# rs485.net
KiCad netlist of a schematic drawn in Altium Designer
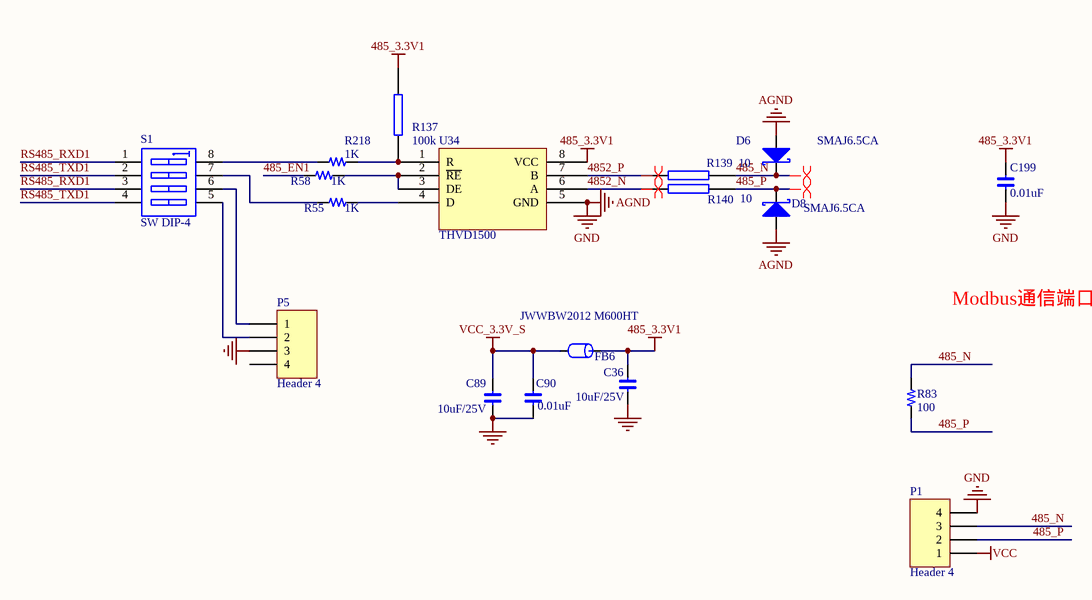
[diagram p0: rs485.SchDoc]

(export (version "E")
  (design (tool "Eeschema 10.0.6"))
  (components
    (comp (ref "C36")
      (value "10uF/25V")
      (footprint "0603C")
      (description "C")
      (libsource (lib "Schlib_20110825") (part "C"))
    )
    (comp (ref "C89")
      (value "10uF/25V")
      (footprint "0603C")
      (description "C")
      (libsource (lib "Schlib_20110825") (part "C"))
    )
    (comp (ref "C90")
      (value "0.01uF")
      (footprint "0603C")
      (description "C")
      (libsource (lib "Schlib_20110825") (part "C"))
    )
    (comp (ref "C199")
      (value "0.01uF")
      (footprint "0603C")
      (description "C")
      (libsource (lib "Schlib_20110825") (part "C"))
    )
    (comp (ref "D6")
      (value "SMAJ6.5CA")
      (footprint "SMA")
      (description "Schottky Diode")
      (libsource (lib "*") (part "DIODE S"))
    )
    (comp (ref "D8")
      (value "SMAJ6.5CA")
      (footprint "SMA")
      (description "Schottky Diode")
      (libsource (lib "*") (part "DIODE S"))
    )
    (comp (ref "FB6")
      (value "JWWBW2012 M600HT")
      (footprint "0805CZ")
      (libsource (lib "Schlib_20110825") (part "FB"))
    )
    (comp (ref "P1")
      (value "Header 4")
      (footprint "4X2.54MMZ")
      (description "Header, 4-Pin")
      (fields (field (name "PUBLISHER") "Altium Limited"))
      (libsource (lib "Miscellaneous Connectors") (part "Header 4"))
    )
    (comp (ref "P5")
      (value "Header 4")
      (footprint "4X2.54MMZ")
      (description "Header, 4-Pin")
      (fields (field (name "PUBLISHER") "Altium Limited"))
      (libsource (lib "") (part "Header 4_1"))
    )
    (comp (ref "R55") (value "1K") (footprint "0603R") (description "R") (libsource (lib "JRJ_1") (part "R")))
    (comp (ref "R58") (value "1K") (footprint "0603R") (description "R") (libsource (lib "JRJ_1") (part "R")))
    (comp (ref "R83")
      (value "100")
      (footprint "0603R")
      (description "R")
      (libsource (lib "JRJ_1") (part "R"))
    )
    (comp (ref "R137") (value "100k") (footprint "0603R") (libsource (lib "*") (part "RES2")))
    (comp (ref "R139") (value "10") (footprint "1206R") (libsource (lib "*") (part "RES2")))
    (comp (ref "R140") (value "10") (footprint "1206R") (libsource (lib "*") (part "RES2")))
    (comp (ref "R218")
      (value "1K")
      (footprint "0603R")
      (description "R")
      (libsource (lib "JRJ_1") (part "R"))
    )
    (comp (ref "S1")
      (value "SW DIP-4")
      (footprint "SW_SMT_8")
      (description "DIP Switch, 4 Position, SPST")
      (fields (field (name "PUBLISHER") "Altium Limited"))
      (libsource (lib "Miscellaneous Devices") (part "SW DIP-4"))
    )
    (comp (ref "U34") (value "THVD1500") (footprint "so-8") (libsource (lib "Schlib1") (part "SN65HVD06D")))
  )
  (nets
    (net (code "1") (name "/485_EN1") (class "Default") (node (ref "R58") (pin "2") (pintype "passive")))
    (net (code "2") (name "/485_N") (class "Default")
      (node (ref "D6") (pin "2") (pinfunction "K_2") (pintype "passive"))
      (node (ref "P1") (pin "3") (pinfunction "3_3") (pintype "passive"))
      (node (ref "R139") (pin "1") (pinfunction "1_1") (pintype "passive"))
      (node (ref "R83") (pin "2") (pintype "passive"))
    )
    (net (code "3") (name "/485_P") (class "Default")
      (node (ref "D8") (pin "2") (pinfunction "K_2") (pintype "passive"))
      (node (ref "P1") (pin "2") (pinfunction "2_2") (pintype "passive"))
      (node (ref "R140") (pin "1") (pinfunction "1_1") (pintype "passive"))
      (node (ref "R83") (pin "1") (pintype "passive"))
    )
    (net (code "4") (name "/4852_N") (class "Default")
      (node (ref "R140") (pin "2") (pinfunction "2_2") (pintype "passive"))
      (node (ref "U34") (pin "6") (pinfunction "A_6") (pintype "passive"))
    )
    (net (code "5") (name "/4852_P") (class "Default")
      (node (ref "R139") (pin "2") (pinfunction "2_2") (pintype "passive"))
      (node (ref "U34") (pin "7") (pinfunction "B_7") (pintype "passive"))
    )
    (net (code "6") (name "/RS485_RXD1") (class "Default")
      (node (ref "S1") (pin "1") (pinfunction "A1_1") (pintype "passive"))
      (node (ref "S1") (pin "3") (pinfunction "A3_3") (pintype "passive"))
    )
    (net (code "7") (name "/RS485_TXD1") (class "Default")
      (node (ref "S1") (pin "2") (pinfunction "A2_2") (pintype "passive"))
      (node (ref "S1") (pin "4") (pinfunction "A4_4") (pintype "passive"))
    )
    (net (code "8") (name "485_3.3V1") (class "Default")
      (node (ref "C199") (pin "2") (pintype "passive"))
      (node (ref "C36") (pin "2") (pintype "passive"))
      (node (ref "FB6") (pin "1") (pintype "passive"))
      (node (ref "R137") (pin "2") (pinfunction "2_2") (pintype "passive"))
      (node (ref "U34") (pin "8") (pinfunction "VCC_8") (pintype "passive"))
    )
    (net (code "9") (name "AGND") (class "Default")
      (node (ref "C199") (pin "1") (pintype "passive"))
      (node (ref "C36") (pin "1") (pintype "passive"))
      (node (ref "C89") (pin "1") (pintype "passive"))
      (node (ref "C90") (pin "1") (pintype "passive"))
      (node (ref "D6") (pin "1") (pinfunction "A_1") (pintype "passive"))
      (node (ref "D8") (pin "1") (pinfunction "A_1") (pintype "passive"))
      (node (ref "P1") (pin "4") (pinfunction "4_4") (pintype "passive"))
      (node (ref "P5") (pin "3") (pinfunction "3_3") (pintype "passive"))
      (node (ref "U34") (pin "5") (pinfunction "GND_5") (pintype "passive"))
    )
    (net (code "10") (name "Net-(S1-B1)") (class "Default")
      (node (ref "R218") (pin "2") (pintype "passive"))
      (node (ref "S1") (pin "8") (pinfunction "B1_8") (pintype "passive"))
    )
    (net (code "11") (name "Net-(S1-B2)") (class "Default")
      (node (ref "R55") (pin "2") (pintype "passive"))
      (node (ref "S1") (pin "7") (pinfunction "B2_7") (pintype "passive"))
    )
    (net (code "12") (name "Net-(S1-B3)") (class "Default")
      (node (ref "P5") (pin "1") (pinfunction "1_1") (pintype "passive"))
      (node (ref "S1") (pin "6") (pinfunction "B3_6") (pintype "passive"))
    )
    (net (code "13") (name "Net-(S1-B4)") (class "Default")
      (node (ref "P5") (pin "2") (pinfunction "2_2") (pintype "passive"))
      (node (ref "S1") (pin "5") (pinfunction "B4_5") (pintype "passive"))
    )
    (net (code "14") (name "Net-(U34-D)") (class "Default")
      (node (ref "R55") (pin "1") (pintype "passive"))
      (node (ref "U34") (pin "4") (pinfunction "D_4") (pintype "passive"))
    )
    (net (code "15") (name "Net-(U34-DE)") (class "Default")
      (node (ref "R58") (pin "1") (pintype "passive"))
      (node (ref "U34") (pin "2") (pinfunction "~{RE}_2") (pintype "passive"))
      (node (ref "U34") (pin "3") (pinfunction "DE_3") (pintype "passive"))
    )
    (net (code "16") (name "Net-(U34-R)") (class "Default")
      (node (ref "R137") (pin "1") (pinfunction "1_1") (pintype "passive"))
      (node (ref "R218") (pin "1") (pintype "passive"))
      (node (ref "U34") (pin "1") (pinfunction "R_1") (pintype "passive"))
    )
    (net (code "17") (name "VCC") (class "Default")
      (node (ref "P1") (pin "1") (pinfunction "1_1") (pintype "passive"))
    )
    (net (code "18") (name "VCC_3.3V_S") (class "Default")
      (node (ref "C89") (pin "2") (pintype "passive"))
      (node (ref "C90") (pin "2") (pintype "passive"))
      (node (ref "FB6") (pin "2") (pintype "passive"))
    )
    (net (code "19") (name "unconnected-(P5-Pad4)") (class "Default")
      (node (ref "P5") (pin "4") (pinfunction "4_4") (pintype "passive"))
    )
  )
)
